# aw_301_runner.net
KiCad netlist of a schematic drawn in EAGLE
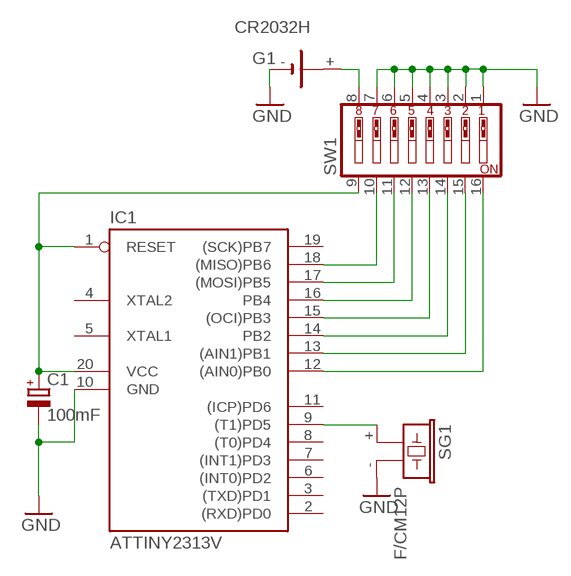
[diagram p0: schematic, sheet 1]

(export (version "E")
  (design (tool "Eeschema 10.0.6"))
  (components
    (comp (ref "C1")
      (value "100mF")
      (footprint "eagle-import:E2,5-6")
      (libsource (lib "eagle-import") (part "CPOL-EUE2.5-6"))
    )
    (comp (ref "G1")
      (value "CR2032H")
      (footprint "eagle-import:CR2032H")
      (libsource (lib "eagle-import") (part "CR2032H"))
    )
    (comp (ref "IC1")
      (value "ATTINY2313V")
      (footprint "eagle-import:DIL20")
      (libsource (lib "eagle-import") (part "AT90S2313P"))
    )
    (comp (ref "SG1")
      (value "F/CM12P")
      (footprint "eagle-import:F_CM12P")
      (libsource (lib "eagle-import") (part "F/CM12P"))
    )
    (comp (ref "SW1")
      (value "SW_DIP-8")
      (footprint "eagle-import:EDG-08")
      (libsource (lib "eagle-import") (part "SW_DIP-8"))
    )
  )
  (nets
    (net (code "1") (name "GND") (class "Default")
      (node (ref "C1") (pin "-") (pinfunction "-_-") (pintype "passive"))
      (node (ref "G1") (pin "-") (pinfunction "-_-") (pintype "passive"))
      (node (ref "IC1") (pin "10") (pinfunction "GND_10") (pintype "power_in"))
      (node (ref "SG1") (pin "-") (pinfunction "2_-") (pintype "passive"))
      (node (ref "SW1") (pin "1") (pinfunction "1_1") (pintype "passive"))
      (node (ref "SW1") (pin "2") (pinfunction "2_2") (pintype "passive"))
      (node (ref "SW1") (pin "3") (pinfunction "3_3") (pintype "passive"))
      (node (ref "SW1") (pin "4") (pinfunction "4_4") (pintype "passive"))
      (node (ref "SW1") (pin "5") (pinfunction "5_5") (pintype "passive"))
      (node (ref "SW1") (pin "6") (pinfunction "6_6") (pintype "passive"))
      (node (ref "SW1") (pin "7") (pinfunction "7_7") (pintype "passive"))
    )
    (net (code "2") (name "Net-(G1-Pad+)") (class "Default")
      (node (ref "G1") (pin "+") (pinfunction "+_+") (pintype "passive"))
      (node (ref "SW1") (pin "8") (pinfunction "8_8") (pintype "passive"))
    )
    (net (code "3") (name "Net-(IC1-(AIN0)PB0)") (class "Default")
      (node (ref "IC1") (pin "12") (pinfunction "(AIN0)PB0_12") (pintype "bidirectional"))
      (node (ref "SW1") (pin "16") (pinfunction "16_16") (pintype "passive"))
    )
    (net (code "4") (name "Net-(IC1-(AIN1)PB1)") (class "Default")
      (node (ref "IC1") (pin "13") (pinfunction "(AIN1)PB1_13") (pintype "bidirectional"))
      (node (ref "SW1") (pin "15") (pinfunction "15_15") (pintype "passive"))
    )
    (net (code "5") (name "Net-(IC1-(MISO)PB6)") (class "Default")
      (node (ref "IC1") (pin "18") (pinfunction "(MISO)PB6_18") (pintype "bidirectional"))
      (node (ref "SW1") (pin "10") (pinfunction "10_10") (pintype "passive"))
    )
    (net (code "6") (name "Net-(IC1-(MOSI)PB5)") (class "Default")
      (node (ref "IC1") (pin "17") (pinfunction "(MOSI)PB5_17") (pintype "bidirectional"))
      (node (ref "SW1") (pin "11") (pinfunction "11_11") (pintype "passive"))
    )
    (net (code "7") (name "Net-(IC1-(OCI)PB3)") (class "Default")
      (node (ref "IC1") (pin "15") (pinfunction "(OCI)PB3_15") (pintype "bidirectional"))
      (node (ref "SW1") (pin "13") (pinfunction "13_13") (pintype "passive"))
    )
    (net (code "8") (name "Net-(IC1-(T1)PD5)") (class "Default")
      (node (ref "IC1") (pin "9") (pinfunction "(T1)PD5_9") (pintype "bidirectional"))
      (node (ref "SG1") (pin "+") (pinfunction "1_+") (pintype "passive"))
    )
    (net (code "9") (name "Net-(IC1-PB2)") (class "Default")
      (node (ref "IC1") (pin "14") (pinfunction "PB2_14") (pintype "bidirectional"))
      (node (ref "SW1") (pin "14") (pinfunction "14_14") (pintype "passive"))
    )
    (net (code "10") (name "Net-(IC1-PB4)") (class "Default")
      (node (ref "IC1") (pin "16") (pinfunction "PB4_16") (pintype "bidirectional"))
      (node (ref "SW1") (pin "12") (pinfunction "12_12") (pintype "passive"))
    )
    (net (code "11") (name "Net-(IC1-RESET)") (class "Default")
      (node (ref "C1") (pin "+") (pinfunction "+_+") (pintype "passive"))
      (node (ref "IC1") (pin "1") (pinfunction "RESET_1") (pintype "bidirectional"))
      (node (ref "IC1") (pin "20") (pinfunction "VCC_20") (pintype "power_in"))
      (node (ref "SW1") (pin "9") (pinfunction "9_9") (pintype "passive"))
    )
    (net (code "12") (name "unconnected-(G1-+-Pad+@1)") (class "Default")
      (node (ref "G1") (pin "+@1") (pinfunction "+_+@1") (pintype "passive"))
    )
    (net (code "13") (name "unconnected-(IC1-(ICP)PD6-Pad11)") (class "Default")
      (node (ref "IC1") (pin "11") (pinfunction "(ICP)PD6_11") (pintype "bidirectional"))
    )
    (net (code "14") (name "unconnected-(IC1-(INT0)PD2-Pad6)") (class "Default")
      (node (ref "IC1") (pin "6") (pinfunction "(INT0)PD2_6") (pintype "bidirectional"))
    )
    (net (code "15") (name "unconnected-(IC1-(INT1)PD3-Pad7)") (class "Default")
      (node (ref "IC1") (pin "7") (pinfunction "(INT1)PD3_7") (pintype "bidirectional"))
    )
    (net (code "16") (name "unconnected-(IC1-(RXD)PD0-Pad2)") (class "Default")
      (node (ref "IC1") (pin "2") (pinfunction "(RXD)PD0_2") (pintype "bidirectional"))
    )
    (net (code "17") (name "unconnected-(IC1-(SCK)PB7-Pad19)") (class "Default")
      (node (ref "IC1") (pin "19") (pinfunction "(SCK)PB7_19") (pintype "bidirectional"))
    )
    (net (code "18") (name "unconnected-(IC1-(T0)PD4-Pad8)") (class "Default")
      (node (ref "IC1") (pin "8") (pinfunction "(T0)PD4_8") (pintype "bidirectional"))
    )
    (net (code "19") (name "unconnected-(IC1-(TXD)PD1-Pad3)") (class "Default")
      (node (ref "IC1") (pin "3") (pinfunction "(TXD)PD1_3") (pintype "bidirectional"))
    )
    (net (code "20") (name "unconnected-(IC1-XTAL1-Pad5)") (class "Default")
      (node (ref "IC1") (pin "5") (pinfunction "XTAL1_5") (pintype "bidirectional"))
    )
    (net (code "21") (name "unconnected-(IC1-XTAL2-Pad4)") (class "Default")
      (node (ref "IC1") (pin "4") (pinfunction "XTAL2_4") (pintype "bidirectional"))
    )
  )
)
